# ProPrj_ftdi-jtag-xilinx_2025-03-12_v3.net
KiCad netlist of a schematic drawn in EasyEDA Pro
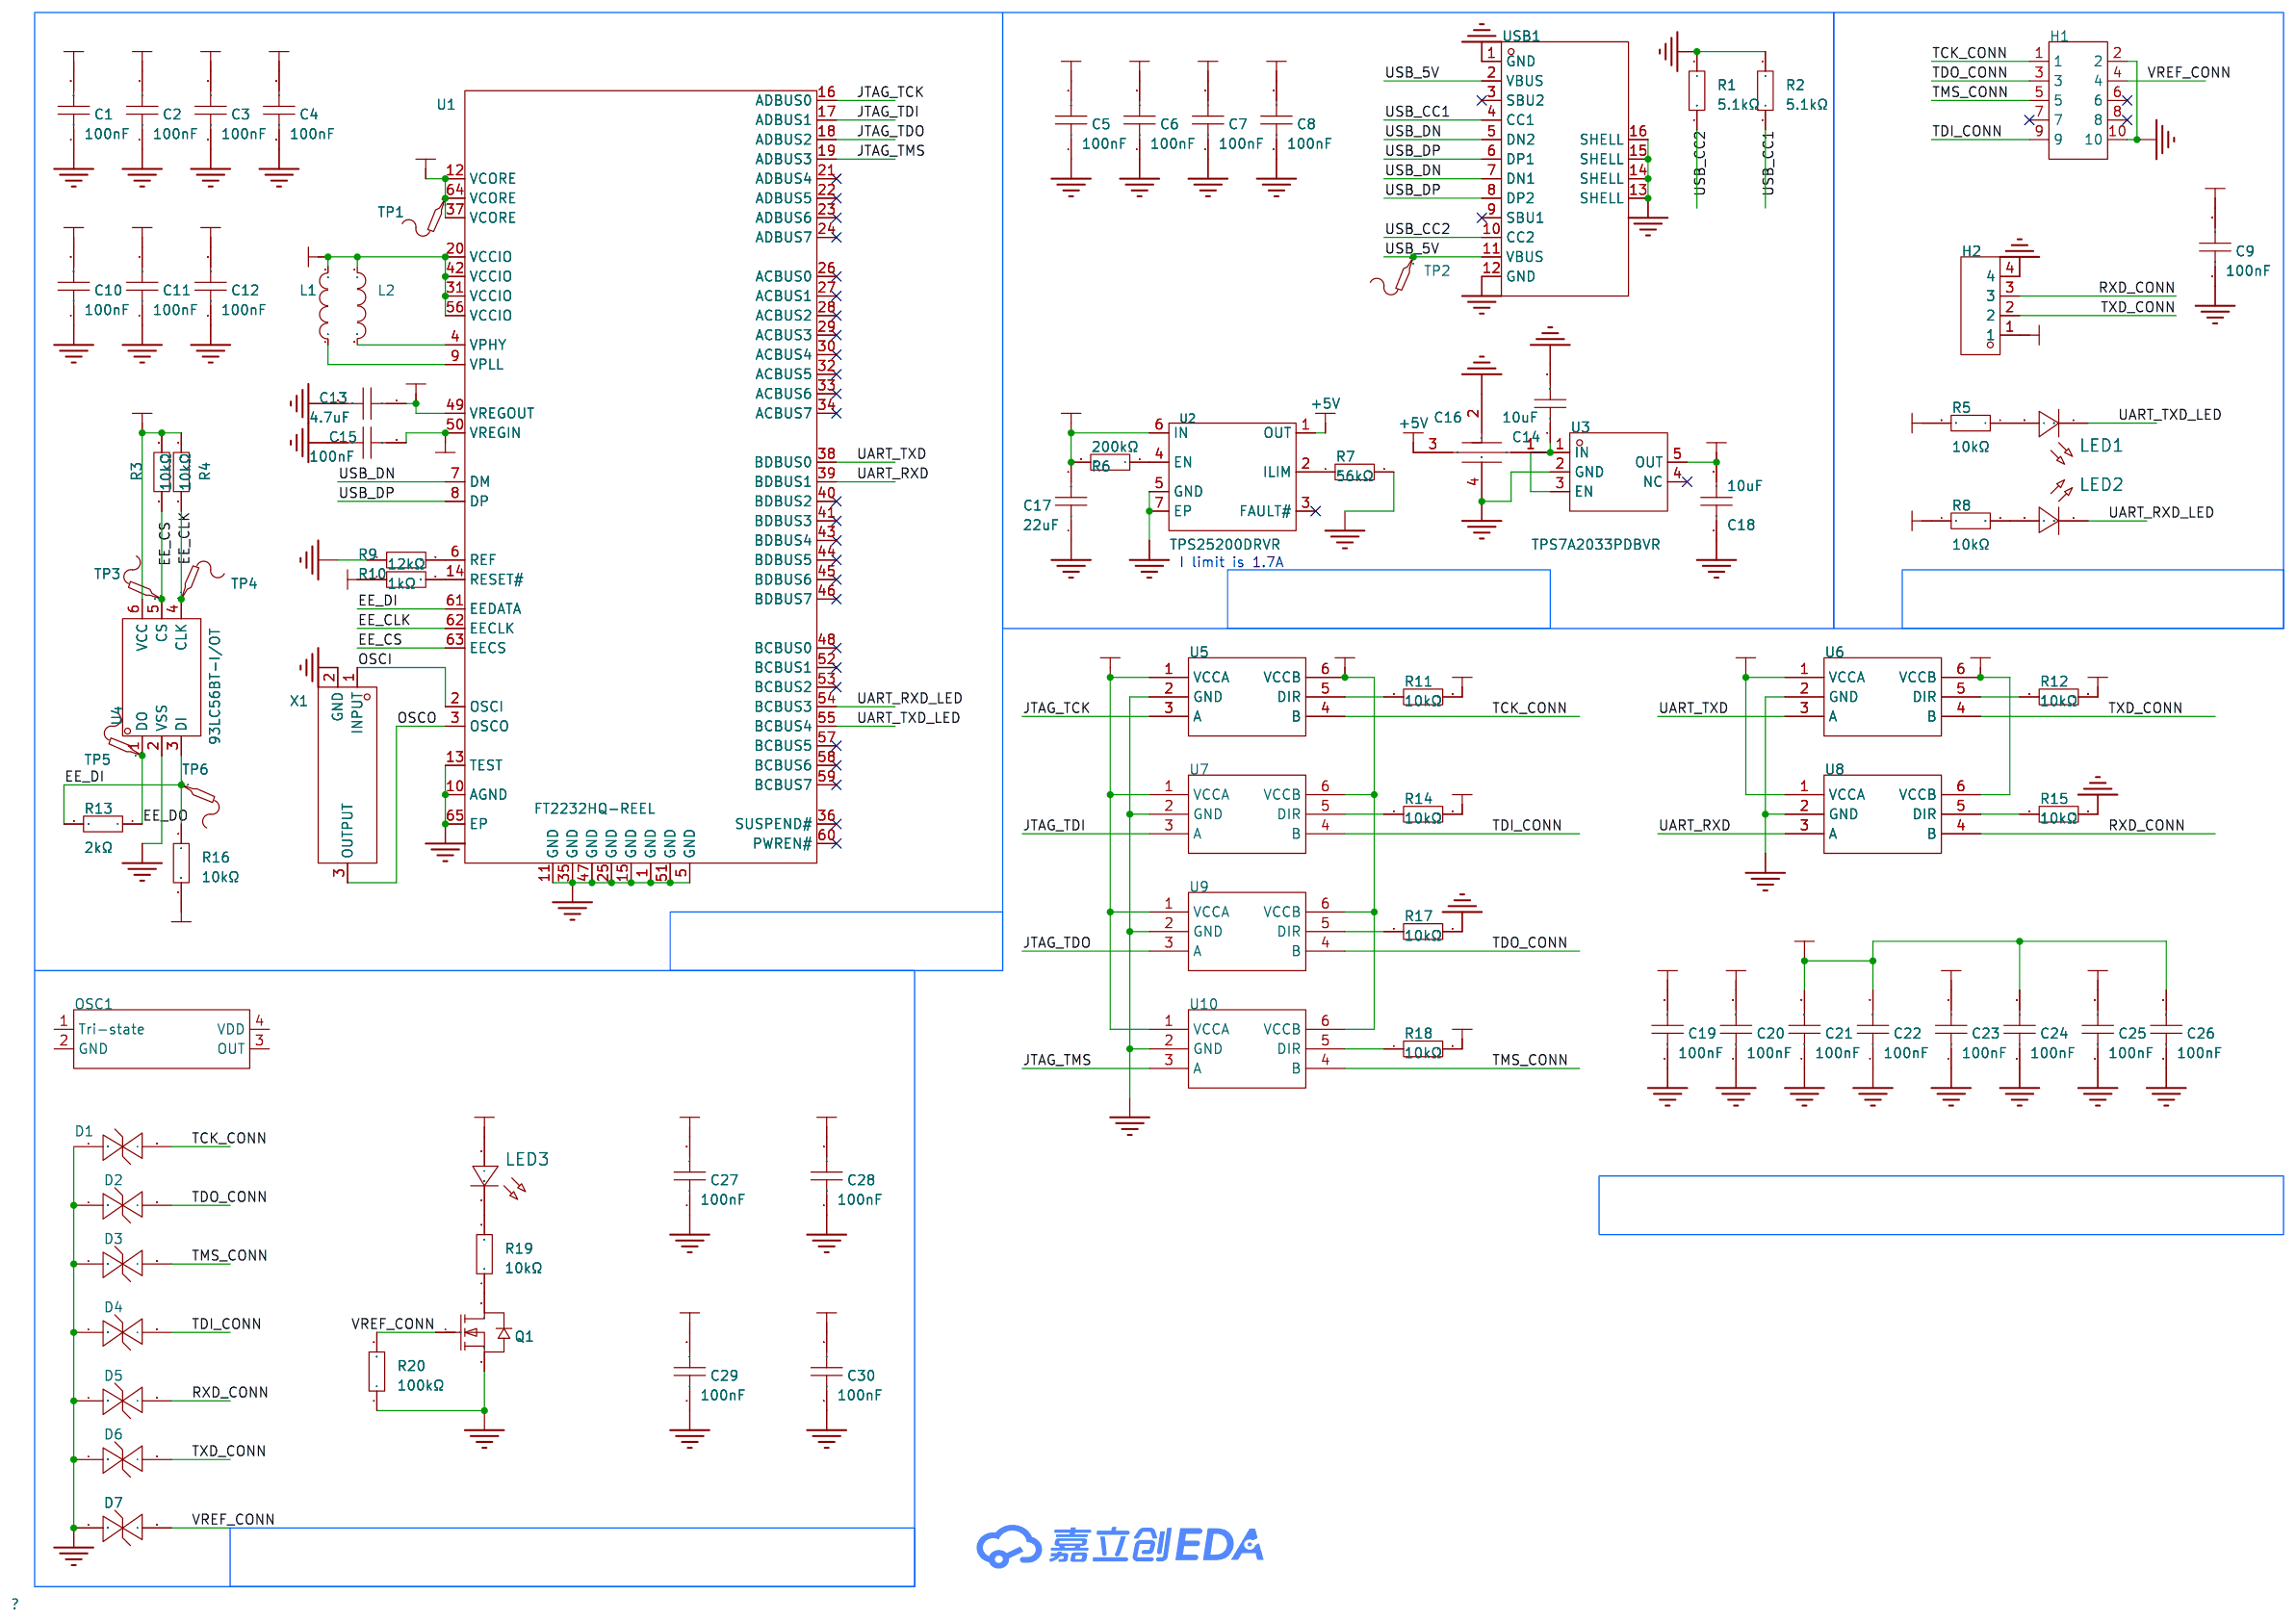
[diagram p0: schematic sheet]

(export (version "E")
  (design (tool "Eeschema 10.0.6"))
  (components
    (comp (ref "C1")
      (value "100nF")
      (footprint "easyedapro:C0603")
      (fields
        (field (name "Manufacturer Part") "CC0402KRX7R7BB104")
        (field (name "Manufacturer") "YAGEO(国巨)")
      )
      (libsource (lib "easyedapro") (part "CapAcitance"))
    )
    (comp (ref "C2")
      (value "100nF")
      (footprint "easyedapro:C0603")
      (fields
        (field (name "Manufacturer Part") "CC0402KRX7R7BB104")
        (field (name "Manufacturer") "YAGEO(国巨)")
      )
      (libsource (lib "easyedapro") (part "CapAcitance"))
    )
    (comp (ref "C3")
      (value "100nF")
      (footprint "easyedapro:C0603")
      (fields
        (field (name "Manufacturer Part") "CC0402KRX7R7BB104")
        (field (name "Manufacturer") "YAGEO(国巨)")
      )
      (libsource (lib "easyedapro") (part "CapAcitance"))
    )
    (comp (ref "C4")
      (value "100nF")
      (footprint "easyedapro:C0603")
      (fields
        (field (name "Manufacturer Part") "CC0402KRX7R7BB104")
        (field (name "Manufacturer") "YAGEO(国巨)")
      )
      (libsource (lib "easyedapro") (part "CapAcitance"))
    )
    (comp (ref "C5")
      (value "100nF")
      (footprint "easyedapro:C0603")
      (fields
        (field (name "Manufacturer Part") "CC0402KRX7R7BB104")
        (field (name "Manufacturer") "YAGEO(国巨)")
      )
      (libsource (lib "easyedapro") (part "CapAcitance"))
    )
    (comp (ref "C6")
      (value "100nF")
      (footprint "easyedapro:C0603")
      (fields
        (field (name "Manufacturer Part") "CC0402KRX7R7BB104")
        (field (name "Manufacturer") "YAGEO(国巨)")
      )
      (libsource (lib "easyedapro") (part "CapAcitance"))
    )
    (comp (ref "C7")
      (value "100nF")
      (footprint "easyedapro:C0603")
      (fields
        (field (name "Manufacturer Part") "CC0402KRX7R7BB104")
        (field (name "Manufacturer") "YAGEO(国巨)")
      )
      (libsource (lib "easyedapro") (part "CapAcitance"))
    )
    (comp (ref "C8")
      (value "100nF")
      (footprint "easyedapro:C0603")
      (fields
        (field (name "Manufacturer Part") "CC0402KRX7R7BB104")
        (field (name "Manufacturer") "YAGEO(国巨)")
      )
      (libsource (lib "easyedapro") (part "CapAcitance"))
    )
    (comp (ref "C9")
      (value "100nF")
      (footprint "easyedapro:C0603")
      (fields
        (field (name "Manufacturer Part") "CC0402KRX7R7BB104")
        (field (name "Manufacturer") "YAGEO(国巨)")
      )
      (libsource (lib "easyedapro") (part "CapAcitance"))
    )
    (comp (ref "C10")
      (value "100nF")
      (footprint "easyedapro:C0603")
      (fields
        (field (name "Manufacturer Part") "CC0402KRX7R7BB104")
        (field (name "Manufacturer") "YAGEO(国巨)")
      )
      (libsource (lib "easyedapro") (part "CapAcitance"))
    )
    (comp (ref "C11")
      (value "100nF")
      (footprint "easyedapro:C0603")
      (fields
        (field (name "Manufacturer Part") "CC0402KRX7R7BB104")
        (field (name "Manufacturer") "YAGEO(国巨)")
      )
      (libsource (lib "easyedapro") (part "CapAcitance"))
    )
    (comp (ref "C12")
      (value "100nF")
      (footprint "easyedapro:C0603")
      (fields
        (field (name "Manufacturer Part") "CC0402KRX7R7BB104")
        (field (name "Manufacturer") "YAGEO(国巨)")
      )
      (libsource (lib "easyedapro") (part "CapAcitance"))
    )
    (comp (ref "C13")
      (value "4.7uF")
      (footprint "easyedapro:C0603")
      (fields
        (field (name "Manufacturer Part") "CL05A475KP5NRNC")
        (field (name "Manufacturer") "SAMSUNG(三星)")
      )
      (libsource (lib "easyedapro") (part "CapAcitance"))
    )
    (comp (ref "C14")
      (value "10uF")
      (footprint "easyedapro:C0603")
      (fields
        (field (name "Manufacturer Part") "CL10A106MA8NRNC")
        (field (name "Manufacturer") "SAMSUNG(三星)")
      )
      (libsource (lib "easyedapro") (part "CapAcitance"))
    )
    (comp (ref "C15")
      (value "100nF")
      (footprint "easyedapro:C0603")
      (fields
        (field (name "Manufacturer Part") "CC0402KRX7R7BB104")
        (field (name "Manufacturer") "YAGEO(国巨)")
      )
      (libsource (lib "easyedapro") (part "CapAcitance"))
    )
    (comp (ref "C16")
      (value "NFM21PC104R1E3D")
      (footprint "easyedapro:CAP-SMD_4P-L2.0-W1.25")
      (description "电容量:100nF;精度:±20%;直流电阻:30mΩ;")
      (fields (field (name "Manufacturer") "muRata(村田)"))
      (libsource (lib "easyedapro") (part "NFM21PC104R1E3D"))
    )
    (comp (ref "C17")
      (value "22uF")
      (footprint "easyedapro:C0603")
      (fields
        (field (name "Manufacturer Part") "CGA0805X5R226M350MT")
        (field (name "Manufacturer") "HRE(芯声)")
      )
      (libsource (lib "easyedapro") (part "CapAcitance"))
    )
    (comp (ref "C18")
      (value "10uF")
      (footprint "easyedapro:C0603")
      (fields
        (field (name "Manufacturer Part") "CL10A106MA8NRNC")
        (field (name "Manufacturer") "SAMSUNG(三星)")
      )
      (libsource (lib "easyedapro") (part "CapAcitance"))
    )
    (comp (ref "C19")
      (value "100nF")
      (footprint "easyedapro:C0603")
      (fields
        (field (name "Manufacturer Part") "CC0402KRX7R7BB104")
        (field (name "Manufacturer") "YAGEO(国巨)")
      )
      (libsource (lib "easyedapro") (part "CapAcitance"))
    )
    (comp (ref "C20")
      (value "100nF")
      (footprint "easyedapro:C0603")
      (fields
        (field (name "Manufacturer Part") "CC0402KRX7R7BB104")
        (field (name "Manufacturer") "YAGEO(国巨)")
      )
      (libsource (lib "easyedapro") (part "CapAcitance"))
    )
    (comp (ref "C21")
      (value "100nF")
      (footprint "easyedapro:C0603")
      (fields
        (field (name "Manufacturer Part") "CC0402KRX7R7BB104")
        (field (name "Manufacturer") "YAGEO(国巨)")
      )
      (libsource (lib "easyedapro") (part "CapAcitance"))
    )
    (comp (ref "C22")
      (value "100nF")
      (footprint "easyedapro:C0603")
      (fields
        (field (name "Manufacturer Part") "CC0402KRX7R7BB104")
        (field (name "Manufacturer") "YAGEO(国巨)")
      )
      (libsource (lib "easyedapro") (part "CapAcitance"))
    )
    (comp (ref "C23")
      (value "100nF")
      (footprint "easyedapro:C0603")
      (fields
        (field (name "Manufacturer Part") "CC0402KRX7R7BB104")
        (field (name "Manufacturer") "YAGEO(国巨)")
      )
      (libsource (lib "easyedapro") (part "CapAcitance"))
    )
    (comp (ref "C24")
      (value "100nF")
      (footprint "easyedapro:C0603")
      (fields
        (field (name "Manufacturer Part") "CC0402KRX7R7BB104")
        (field (name "Manufacturer") "YAGEO(国巨)")
      )
      (libsource (lib "easyedapro") (part "CapAcitance"))
    )
    (comp (ref "C25")
      (value "100nF")
      (footprint "easyedapro:C0603")
      (fields
        (field (name "Manufacturer Part") "CC0402KRX7R7BB104")
        (field (name "Manufacturer") "YAGEO(国巨)")
      )
      (libsource (lib "easyedapro") (part "CapAcitance"))
    )
    (comp (ref "C26")
      (value "100nF")
      (footprint "easyedapro:C0603")
      (fields
        (field (name "Manufacturer Part") "CC0402KRX7R7BB104")
        (field (name "Manufacturer") "YAGEO(国巨)")
      )
      (libsource (lib "easyedapro") (part "CapAcitance"))
    )
    (comp (ref "C27")
      (value "100nF")
      (footprint "easyedapro:C0603")
      (fields
        (field (name "Manufacturer Part") "CC0402KRX7R7BB104")
        (field (name "Manufacturer") "YAGEO(国巨)")
      )
      (libsource (lib "easyedapro") (part "CapAcitance"))
    )
    (comp (ref "C28")
      (value "100nF")
      (footprint "easyedapro:C0603")
      (fields
        (field (name "Manufacturer Part") "CC0402KRX7R7BB104")
        (field (name "Manufacturer") "YAGEO(国巨)")
      )
      (libsource (lib "easyedapro") (part "CapAcitance"))
    )
    (comp (ref "C29")
      (value "100nF")
      (footprint "easyedapro:C0603")
      (fields
        (field (name "Manufacturer Part") "CC0402KRX7R7BB104")
        (field (name "Manufacturer") "YAGEO(国巨)")
      )
      (libsource (lib "easyedapro") (part "CapAcitance"))
    )
    (comp (ref "C30")
      (value "100nF")
      (footprint "easyedapro:C0603")
      (fields
        (field (name "Manufacturer Part") "CC0402KRX7R7BB104")
        (field (name "Manufacturer") "YAGEO(国巨)")
      )
      (libsource (lib "easyedapro") (part "CapAcitance"))
    )
    (comp (ref "D1")
      (value "H5VL10B")
      (footprint "easyedapro:SOD-882_L1.0-W0.6-BI")
      (description "极性:双向;反向截止电压(Vrwm):5V;最大钳位电压:10V;峰值脉冲电流(Ipp):5A;峰值脉冲功率(Ppp):50W;击穿电压:5.6V;")
      (fields (field (name "Manufacturer") "宏迦橙"))
      (libsource (lib "easyedapro") (part "H5VL10B"))
    )
    (comp (ref "D2")
      (value "H5VL10B")
      (footprint "easyedapro:SOD-882_L1.0-W0.6-BI")
      (description "极性:双向;反向截止电压(Vrwm):5V;最大钳位电压:10V;峰值脉冲电流(Ipp):5A;峰值脉冲功率(Ppp):50W;击穿电压:5.6V;")
      (fields (field (name "Manufacturer") "宏迦橙"))
      (libsource (lib "easyedapro") (part "H5VL10B"))
    )
    (comp (ref "D3")
      (value "H5VL10B")
      (footprint "easyedapro:SOD-882_L1.0-W0.6-BI")
      (description "极性:双向;反向截止电压(Vrwm):5V;最大钳位电压:10V;峰值脉冲电流(Ipp):5A;峰值脉冲功率(Ppp):50W;击穿电压:5.6V;")
      (fields (field (name "Manufacturer") "宏迦橙"))
      (libsource (lib "easyedapro") (part "H5VL10B"))
    )
    (comp (ref "D4")
      (value "H5VL10B")
      (footprint "easyedapro:SOD-882_L1.0-W0.6-BI")
      (description "极性:双向;反向截止电压(Vrwm):5V;最大钳位电压:10V;峰值脉冲电流(Ipp):5A;峰值脉冲功率(Ppp):50W;击穿电压:5.6V;")
      (fields (field (name "Manufacturer") "宏迦橙"))
      (libsource (lib "easyedapro") (part "H5VL10B"))
    )
    (comp (ref "D5")
      (value "H5VL10B")
      (footprint "easyedapro:SOD-882_L1.0-W0.6-BI")
      (description "极性:双向;反向截止电压(Vrwm):5V;最大钳位电压:10V;峰值脉冲电流(Ipp):5A;峰值脉冲功率(Ppp):50W;击穿电压:5.6V;")
      (fields (field (name "Manufacturer") "宏迦橙"))
      (libsource (lib "easyedapro") (part "H5VL10B"))
    )
    (comp (ref "D6")
      (value "H5VL10B")
      (footprint "easyedapro:SOD-882_L1.0-W0.6-BI")
      (description "极性:双向;反向截止电压(Vrwm):5V;最大钳位电压:10V;峰值脉冲电流(Ipp):5A;峰值脉冲功率(Ppp):50W;击穿电压:5.6V;")
      (fields (field (name "Manufacturer") "宏迦橙"))
      (libsource (lib "easyedapro") (part "H5VL10B"))
    )
    (comp (ref "D7")
      (value "H5VL10B")
      (footprint "easyedapro:SOD-882_L1.0-W0.6-BI")
      (description "极性:双向;反向截止电压(Vrwm):5V;最大钳位电压:10V;峰值脉冲电流(Ipp):5A;峰值脉冲功率(Ppp):50W;击穿电压:5.6V;")
      (fields (field (name "Manufacturer") "宏迦橙"))
      (libsource (lib "easyedapro") (part "H5VL10B"))
    )
    (comp (ref "H1")
      (value "PZ254-2-05-Z-8.5")
      (footprint "easyedapro:HDR-TH_10P-P2.54-V-M-R2-C5-S2.54")
      (fields (field (name "Manufacturer") "HCTL(华灿天禄)"))
      (libsource (lib "easyedapro") (part "PZ254-2-05-Z-8.5"))
    )
    (comp (ref "H2")
      (value "PZ254V-11-04P")
      (footprint "easyedapro:HDR-TH_4P-P2.54-V-M")
      (fields (field (name "Manufacturer") "XFCN(兴飞)"))
      (libsource (lib "easyedapro") (part "PZ254V-11-04P_C2691448"))
    )
    (comp (ref "L1")
      (value "BLM15PD121SN1D")
      (footprint "easyedapro:L0402")
      (description "标称阻抗@测试频率:120Ω@100MHz;误差:±25%;直流电阻(RDC):90mΩ;")
      (fields (field (name "Manufacturer") "muRata(村田)"))
      (libsource (lib "easyedapro") (part "BLM15PD121SN1D"))
    )
    (comp (ref "L2")
      (value "BLM15PD121SN1D")
      (footprint "easyedapro:L0402")
      (description "标称阻抗@测试频率:120Ω@100MHz;误差:±25%;直流电阻(RDC):90mΩ;")
      (fields (field (name "Manufacturer") "muRata(村田)"))
      (libsource (lib "easyedapro") (part "BLM15PD121SN1D"))
    )
    (comp (ref "LED1")
      (value "NCD0603Y1")
      (footprint "easyedapro:LED_0603")
      (fields (field (name "Manufacturer") "国星光电"))
      (libsource (lib "easyedapro") (part "LED_R"))
    )
    (comp (ref "LED2")
      (value "NCD0603Y1")
      (footprint "easyedapro:LED_0603")
      (fields (field (name "Manufacturer") "国星光电"))
      (libsource (lib "easyedapro") (part "LED_R"))
    )
    (comp (ref "LED3")
      (value "NCD0603Y1")
      (footprint "easyedapro:LED_0603")
      (fields (field (name "Manufacturer") "国星光电"))
      (libsource (lib "easyedapro") (part "LED_R"))
    )
    (comp (ref "OSC1")
      (value "12MHz")
      (footprint "easyedapro:OSC-SMD_4P-L2.0-W1.6-BL")
      (description "频率:12MHz;常温频差:±10ppm;输出模式:CMOS;工作电压:1.8V~3.3V;频率稳定度:±20ppm;")
      (fields
        (field (name "Manufacturer Part") "OT7EL89CJI-111YLC-12M")
        (field (name "Manufacturer") "YXC(扬兴晶振)")
      )
      (libsource (lib "easyedapro") (part "OT7EL89CJI-111YLC-12M"))
    )
    (comp (ref "Q1")
      (value "SI2302")
      (footprint "easyedapro:SOT-23-3_L2.9-W1.3-P1.90-LS2.4-BR")
      (description "类型:1个N沟道;漏源电压(Vdss):20V;连续漏极电流(Id):3A;导通电阻(RDS(on)):50mΩ@4.5V,3A;耗散功率(Pd):1W;阈值电压(Vgs(th)):1V;")
      (fields (field (name "Manufacturer") "YONGYUTAI(永裕泰)"))
      (libsource (lib "easyedapro") (part "SI2302_C2891732"))
    )
    (comp (ref "R1")
      (value "5.1kΩ")
      (footprint "easyedapro:R0603")
      (fields
        (field (name "Manufacturer Part") "0402WGF5101TCE")
        (field (name "Manufacturer") "UNI-ROYAL(厚声)")
      )
      (libsource (lib "easyedapro") (part "电阻"))
    )
    (comp (ref "R2")
      (value "5.1kΩ")
      (footprint "easyedapro:R0603")
      (fields
        (field (name "Manufacturer Part") "0402WGF5101TCE")
        (field (name "Manufacturer") "UNI-ROYAL(厚声)")
      )
      (libsource (lib "easyedapro") (part "电阻"))
    )
    (comp (ref "R3")
      (value "10kΩ")
      (footprint "easyedapro:R0603")
      (fields (field (name "Manufacturer Part") "RC0402FR-0710KL") (field (name "Manufacturer") "YAGEO(国巨)"))
      (libsource (lib "easyedapro") (part "电阻"))
    )
    (comp (ref "R4")
      (value "10kΩ")
      (footprint "easyedapro:R0603")
      (fields (field (name "Manufacturer Part") "RC0402FR-0710KL") (field (name "Manufacturer") "YAGEO(国巨)"))
      (libsource (lib "easyedapro") (part "电阻"))
    )
    (comp (ref "R5")
      (value "10kΩ")
      (footprint "easyedapro:R0603")
      (fields (field (name "Manufacturer Part") "RC0402FR-0710KL") (field (name "Manufacturer") "YAGEO(国巨)"))
      (libsource (lib "easyedapro") (part "电阻"))
    )
    (comp (ref "R6")
      (value "200kΩ")
      (footprint "easyedapro:R0603")
      (fields
        (field (name "Manufacturer Part") "0402WGF2003TCE")
        (field (name "Manufacturer") "UNI-ROYAL(厚声)")
      )
      (libsource (lib "easyedapro") (part "电阻"))
    )
    (comp (ref "R7")
      (value "56kΩ")
      (footprint "easyedapro:R0603")
      (fields
        (field (name "Manufacturer Part") "0402WGF5602TCE")
        (field (name "Manufacturer") "UNI-ROYAL(厚声)")
      )
      (libsource (lib "easyedapro") (part "电阻"))
    )
    (comp (ref "R8")
      (value "10kΩ")
      (footprint "easyedapro:R0603")
      (fields (field (name "Manufacturer Part") "RC0402FR-0710KL") (field (name "Manufacturer") "YAGEO(国巨)"))
      (libsource (lib "easyedapro") (part "电阻"))
    )
    (comp (ref "R9")
      (value "12kΩ")
      (footprint "easyedapro:R0603")
      (fields
        (field (name "Manufacturer Part") "0402WGF1202TCE")
        (field (name "Manufacturer") "UNI-ROYAL(厚声)")
      )
      (libsource (lib "easyedapro") (part "电阻"))
    )
    (comp (ref "R10")
      (value "1kΩ")
      (footprint "easyedapro:R0603")
      (fields
        (field (name "Manufacturer Part") "0402WGF1001TCE")
        (field (name "Manufacturer") "UNI-ROYAL(厚声)")
      )
      (libsource (lib "easyedapro") (part "电阻"))
    )
    (comp (ref "R11")
      (value "10kΩ")
      (footprint "easyedapro:R0603")
      (fields (field (name "Manufacturer Part") "RC0402FR-0710KL") (field (name "Manufacturer") "YAGEO(国巨)"))
      (libsource (lib "easyedapro") (part "电阻"))
    )
    (comp (ref "R12")
      (value "10kΩ")
      (footprint "easyedapro:R0603")
      (fields (field (name "Manufacturer Part") "RC0402FR-0710KL") (field (name "Manufacturer") "YAGEO(国巨)"))
      (libsource (lib "easyedapro") (part "电阻"))
    )
    (comp (ref "R13")
      (value "2kΩ")
      (footprint "easyedapro:R0603")
      (fields (field (name "Manufacturer Part") "FRC0402F2001TS") (field (name "Manufacturer") "FOJAN(富捷)"))
      (libsource (lib "easyedapro") (part "电阻"))
    )
    (comp (ref "R14")
      (value "10kΩ")
      (footprint "easyedapro:R0603")
      (fields (field (name "Manufacturer Part") "RC0402FR-0710KL") (field (name "Manufacturer") "YAGEO(国巨)"))
      (libsource (lib "easyedapro") (part "电阻"))
    )
    (comp (ref "R15")
      (value "10kΩ")
      (footprint "easyedapro:R0603")
      (fields (field (name "Manufacturer Part") "RC0402FR-0710KL") (field (name "Manufacturer") "YAGEO(国巨)"))
      (libsource (lib "easyedapro") (part "电阻"))
    )
    (comp (ref "R16")
      (value "10kΩ")
      (footprint "easyedapro:R0603")
      (fields (field (name "Manufacturer Part") "RC0402FR-0710KL") (field (name "Manufacturer") "YAGEO(国巨)"))
      (libsource (lib "easyedapro") (part "电阻"))
    )
    (comp (ref "R17")
      (value "10kΩ")
      (footprint "easyedapro:R0603")
      (fields (field (name "Manufacturer Part") "RC0402FR-0710KL") (field (name "Manufacturer") "YAGEO(国巨)"))
      (libsource (lib "easyedapro") (part "电阻"))
    )
    (comp (ref "R18")
      (value "10kΩ")
      (footprint "easyedapro:R0603")
      (fields (field (name "Manufacturer Part") "RC0402FR-0710KL") (field (name "Manufacturer") "YAGEO(国巨)"))
      (libsource (lib "easyedapro") (part "电阻"))
    )
    (comp (ref "R19")
      (value "10kΩ")
      (footprint "easyedapro:R0603")
      (fields (field (name "Manufacturer Part") "RC0402FR-0710KL") (field (name "Manufacturer") "YAGEO(国巨)"))
      (libsource (lib "easyedapro") (part "电阻"))
    )
    (comp (ref "R20")
      (value "100kΩ")
      (footprint "easyedapro:R0402")
      (description "电阻类型:厚膜电阻;阻值:100kΩ;精度:±1%;功率:62.5mW;最大工作电压:50V;温度系数:±100ppm/°C;")
      (fields
        (field (name "Manufacturer Part") "0402WGF1003TCE")
        (field (name "Manufacturer") "UNI-ROYAL(厚声)")
      )
      (libsource (lib "easyedapro") (part "0402WGF1003TCE"))
    )
    (comp (ref "TP1")
      (value "~")
      (footprint "easyedapro:Test-Point-0.5mm")
      (description "Test Point 测试点")
      (libsource (lib "easyedapro") (part "Test-Point"))
    )
    (comp (ref "TP2")
      (value "~")
      (footprint "easyedapro:Test-Point-0.5mm")
      (description "Test Point 测试点")
      (libsource (lib "easyedapro") (part "Test-Point"))
    )
    (comp (ref "TP3")
      (value "~")
      (footprint "easyedapro:Test-Point-0.5mm")
      (description "Test Point 测试点")
      (libsource (lib "easyedapro") (part "Test-Point"))
    )
    (comp (ref "TP4")
      (value "~")
      (footprint "easyedapro:Test-Point-0.5mm")
      (description "Test Point 测试点")
      (libsource (lib "easyedapro") (part "Test-Point"))
    )
    (comp (ref "TP5")
      (value "~")
      (footprint "easyedapro:Test-Point-0.5mm")
      (description "Test Point 测试点")
      (libsource (lib "easyedapro") (part "Test-Point"))
    )
    (comp (ref "TP6")
      (value "~")
      (footprint "easyedapro:Test-Point-0.5mm")
      (description "Test Point 测试点")
      (libsource (lib "easyedapro") (part "Test-Point"))
    )
    (comp (ref "U1")
      (value "FT2232HQ-REEL")
      (footprint "easyedapro:QFN-64_L9.0-W9.0-P0.50-TL-EP4.3")
      (description "应用功能:USB转UART；USB转FIFO;接口协议:UART;供电电压:3V~3.6V;")
      (fields (field (name "Manufacturer") "FTDI(飞特帝亚)"))
      (libsource (lib "easyedapro") (part "FT2232HQ-REEL"))
    )
    (comp (ref "U2")
      (value "TPS25200DRVR")
      (footprint "easyedapro:WSON-6_L2.0-W2.0-P0.65-TL-EP")
      (description "TPS25200 具有过压钳位的 6.5V/2.8A 电子保险丝")
      (fields (field (name "Manufacturer") "TI(德州仪器)"))
      (libsource (lib "easyedapro") (part "TPS25200DRVR"))
    )
    (comp (ref "U3")
      (value "TPS7A2033PDBVR")
      (footprint "easyedapro:SOT-23-5_L2.9-W1.6-P0.95-LS2.8-BR")
      (fields (field (name "Manufacturer") "TI(德州仪器)"))
      (libsource (lib "easyedapro") (part "TPS7A2033PDBVR"))
    )
    (comp (ref "U4")
      (value "93LC56BT-I/OT")
      (footprint "easyedapro:SOT-23-6_L2.9-W1.6-P0.95-LS2.8-BR")
      (fields (field (name "Manufacturer") "MICROCHIP(美国微芯)"))
      (libsource (lib "easyedapro") (part "93LC56BT-I/OT"))
    )
    (comp (ref "U5")
      (value "SN74LVC1T45DBVR")
      (footprint "easyedapro:SOT-23-6_L2.9-W1.6-P0.95-LS2.8-BR")
      (description "数据速率:420Mbps;电压(VCCA):1.65V~5.5V;电压(VCCB):1.65V~5.5V;电路数:1;每个电路通道数:1;")
      (fields (field (name "Manufacturer") "TI(德州仪器)"))
      (libsource (lib "easyedapro") (part "SN74LVC1T45DBVR"))
    )
    (comp (ref "U6")
      (value "SN74LVC1T45DBVR")
      (footprint "easyedapro:SOT-23-6_L2.9-W1.6-P0.95-LS2.8-BR")
      (description "数据速率:420Mbps;电压(VCCA):1.65V~5.5V;电压(VCCB):1.65V~5.5V;电路数:1;每个电路通道数:1;")
      (fields (field (name "Manufacturer") "TI(德州仪器)"))
      (libsource (lib "easyedapro") (part "SN74LVC1T45DBVR"))
    )
    (comp (ref "U7")
      (value "SN74LVC1T45DBVR")
      (footprint "easyedapro:SOT-23-6_L2.9-W1.6-P0.95-LS2.8-BR")
      (description "数据速率:420Mbps;电压(VCCA):1.65V~5.5V;电压(VCCB):1.65V~5.5V;电路数:1;每个电路通道数:1;")
      (fields (field (name "Manufacturer") "TI(德州仪器)"))
      (libsource (lib "easyedapro") (part "SN74LVC1T45DBVR"))
    )
    (comp (ref "U8")
      (value "SN74LVC1T45DBVR")
      (footprint "easyedapro:SOT-23-6_L2.9-W1.6-P0.95-LS2.8-BR")
      (description "数据速率:420Mbps;电压(VCCA):1.65V~5.5V;电压(VCCB):1.65V~5.5V;电路数:1;每个电路通道数:1;")
      (fields (field (name "Manufacturer") "TI(德州仪器)"))
      (libsource (lib "easyedapro") (part "SN74LVC1T45DBVR"))
    )
    (comp (ref "U9")
      (value "SN74LVC1T45DBVR")
      (footprint "easyedapro:SOT-23-6_L2.9-W1.6-P0.95-LS2.8-BR")
      (description "数据速率:420Mbps;电压(VCCA):1.65V~5.5V;电压(VCCB):1.65V~5.5V;电路数:1;每个电路通道数:1;")
      (fields (field (name "Manufacturer") "TI(德州仪器)"))
      (libsource (lib "easyedapro") (part "SN74LVC1T45DBVR"))
    )
    (comp (ref "U10")
      (value "SN74LVC1T45DBVR")
      (footprint "easyedapro:SOT-23-6_L2.9-W1.6-P0.95-LS2.8-BR")
      (description "数据速率:420Mbps;电压(VCCA):1.65V~5.5V;电压(VCCB):1.65V~5.5V;电路数:1;每个电路通道数:1;")
      (fields (field (name "Manufacturer") "TI(德州仪器)"))
      (libsource (lib "easyedapro") (part "SN74LVC1T45DBVR"))
    )
    (comp (ref "USB1")
      (value "TYPEC-302-BRP16SC16")
      (footprint "easyedapro:USB-C-SMD_TYPEC-302-BRP16SC16")
      (fields (field (name "Manufacturer") "XUNPU(讯普)"))
      (libsource (lib "easyedapro") (part "TYPEC-302-BRP16SC16"))
    )
    (comp (ref "X1")
      (value "12MHz")
      (footprint "easyedapro:CRYSTAL-SMD_3P-L3.2-W1.3-P1.2-BL")
      (description "频率:12MHz;内置负载电容:10pF;谐振阻抗:30Ω;")
      (fields
        (field (name "Manufacturer Part") "CSTNE12M0G52A000R0")
        (field (name "Manufacturer") "muRata(村田)")
      )
      (libsource (lib "easyedapro") (part "CSTNE12M0G52A000R0"))
    )
  )
  (nets
    (net (code "1") (name "+5V") (class "Default")
      (node (ref "C16") (pin "3") (pinfunction "OUT_3") (pintype "input"))
      (node (ref "U2") (pin "1") (pinfunction "OUT_1") (pintype "input"))
    )
    (net (code "2") (name "/EE_CLK") (class "Default")
      (node (ref "R4") (pin "2") (pinfunction "2_2") (pintype "input"))
      (node (ref "TP4") (pin "1") (pinfunction "1_1") (pintype "input"))
      (node (ref "U1") (pin "62") (pinfunction "EECLK_62") (pintype "input"))
      (node (ref "U4") (pin "4") (pinfunction "CLK_4") (pintype "input"))
    )
    (net (code "3") (name "/EE_CS") (class "Default")
      (node (ref "R3") (pin "2") (pinfunction "2_2") (pintype "input"))
      (node (ref "TP3") (pin "1") (pinfunction "1_1") (pintype "input"))
      (node (ref "U1") (pin "63") (pinfunction "EECS_63") (pintype "input"))
      (node (ref "U4") (pin "5") (pinfunction "CS_5") (pintype "input"))
    )
    (net (code "4") (name "/EE_DI") (class "Default")
      (node (ref "R13") (pin "2") (pinfunction "2_2") (pintype "input"))
      (node (ref "R16") (pin "1") (pinfunction "1_1") (pintype "input"))
      (node (ref "TP6") (pin "1") (pinfunction "1_1") (pintype "input"))
      (node (ref "U1") (pin "61") (pinfunction "EEDATA_61") (pintype "input"))
      (node (ref "U4") (pin "3") (pinfunction "DI_3") (pintype "input"))
    )
    (net (code "5") (name "/EE_DO") (class "Default")
      (node (ref "R13") (pin "1") (pinfunction "1_1") (pintype "input"))
      (node (ref "TP5") (pin "1") (pinfunction "1_1") (pintype "input"))
      (node (ref "U4") (pin "1") (pinfunction "DO_1") (pintype "input"))
    )
    (net (code "6") (name "/JTAG_TCK") (class "Default")
      (node (ref "U1") (pin "16") (pinfunction "ADBUS0_16") (pintype "input"))
      (node (ref "U5") (pin "3") (pinfunction "A_3") (pintype "unspecified"))
    )
    (net (code "7") (name "/JTAG_TDI") (class "Default")
      (node (ref "U1") (pin "17") (pinfunction "ADBUS1_17") (pintype "input"))
      (node (ref "U7") (pin "3") (pinfunction "A_3") (pintype "unspecified"))
    )
    (net (code "8") (name "/JTAG_TDO") (class "Default")
      (node (ref "U1") (pin "18") (pinfunction "ADBUS2_18") (pintype "input"))
      (node (ref "U9") (pin "3") (pinfunction "A_3") (pintype "unspecified"))
    )
    (net (code "9") (name "/JTAG_TMS") (class "Default")
      (node (ref "U1") (pin "19") (pinfunction "ADBUS3_19") (pintype "input"))
      (node (ref "U10") (pin "3") (pinfunction "A_3") (pintype "unspecified"))
    )
    (net (code "10") (name "/OSCI") (class "Default")
      (node (ref "U1") (pin "2") (pinfunction "OSCI_2") (pintype "input"))
      (node (ref "X1") (pin "1") (pinfunction "INPUT_1") (pintype "unspecified"))
    )
    (net (code "11") (name "/OSCO") (class "Default")
      (node (ref "U1") (pin "3") (pinfunction "OSCO_3") (pintype "input"))
      (node (ref "X1") (pin "3") (pinfunction "OUTPUT_3") (pintype "unspecified"))
    )
    (net (code "12") (name "/RXD_CONN") (class "Default")
      (node (ref "D5") (pin "2") (pinfunction "A_2") (pintype "unspecified"))
      (node (ref "H2") (pin "3") (pinfunction "3_3") (pintype "unspecified"))
      (node (ref "U8") (pin "4") (pinfunction "B_4") (pintype "unspecified"))
    )
    (net (code "13") (name "/TCK_CONN") (class "Default")
      (node (ref "D1") (pin "2") (pinfunction "A_2") (pintype "unspecified"))
      (node (ref "H1") (pin "1") (pinfunction "1_1") (pintype "unspecified"))
      (node (ref "U5") (pin "4") (pinfunction "B_4") (pintype "unspecified"))
    )
    (net (code "14") (name "/TDI_CONN") (class "Default")
      (node (ref "D4") (pin "2") (pinfunction "A_2") (pintype "unspecified"))
      (node (ref "H1") (pin "9") (pinfunction "9_9") (pintype "unspecified"))
      (node (ref "U7") (pin "4") (pinfunction "B_4") (pintype "unspecified"))
    )
    (net (code "15") (name "/TDO_CONN") (class "Default")
      (node (ref "D2") (pin "2") (pinfunction "A_2") (pintype "unspecified"))
      (node (ref "H1") (pin "3") (pinfunction "3_3") (pintype "unspecified"))
      (node (ref "U9") (pin "4") (pinfunction "B_4") (pintype "unspecified"))
    )
    (net (code "16") (name "/TMS_CONN") (class "Default")
      (node (ref "D3") (pin "2") (pinfunction "A_2") (pintype "unspecified"))
      (node (ref "H1") (pin "5") (pinfunction "5_5") (pintype "unspecified"))
      (node (ref "U10") (pin "4") (pinfunction "B_4") (pintype "unspecified"))
    )
    (net (code "17") (name "/TXD_CONN") (class "Default")
      (node (ref "D6") (pin "2") (pinfunction "A_2") (pintype "unspecified"))
      (node (ref "H2") (pin "2") (pinfunction "2_2") (pintype "unspecified"))
      (node (ref "U6") (pin "4") (pinfunction "B_4") (pintype "unspecified"))
    )
    (net (code "18") (name "/UART_RXD") (class "Default")
      (node (ref "U1") (pin "39") (pinfunction "BDBUS1_39") (pintype "input"))
      (node (ref "U8") (pin "3") (pinfunction "A_3") (pintype "unspecified"))
    )
    (net (code "19") (name "/UART_RXD_LED") (class "Default")
      (node (ref "LED2") (pin "1") (pinfunction "C_1") (pintype "input"))
      (node (ref "U1") (pin "54") (pinfunction "BCBUS3_54") (pintype "input"))
    )
    (net (code "20") (name "/UART_TXD") (class "Default")
      (node (ref "U1") (pin "38") (pinfunction "BDBUS0_38") (pintype "input"))
      (node (ref "U6") (pin "3") (pinfunction "A_3") (pintype "unspecified"))
    )
    (net (code "21") (name "/UART_TXD_LED") (class "Default")
      (node (ref "LED1") (pin "1") (pinfunction "C_1") (pintype "input"))
      (node (ref "U1") (pin "55") (pinfunction "BCBUS4_55") (pintype "input"))
    )
    (net (code "22") (name "/USB_CC1") (class "Default")
      (node (ref "R2") (pin "2") (pinfunction "2_2") (pintype "input"))
      (node (ref "USB1") (pin "4") (pinfunction "CC1_4") (pintype "unspecified"))
    )
    (net (code "23") (name "/USB_CC2") (class "Default")
      (node (ref "R1") (pin "2") (pinfunction "2_2") (pintype "input"))
      (node (ref "USB1") (pin "10") (pinfunction "CC2_10") (pintype "unspecified"))
    )
    (net (code "24") (name "/USB_DN") (class "Default")
      (node (ref "U1") (pin "7") (pinfunction "DM_7") (pintype "input"))
      (node (ref "USB1") (pin "5") (pinfunction "DN2_5") (pintype "unspecified"))
      (node (ref "USB1") (pin "7") (pinfunction "DN1_7") (pintype "unspecified"))
    )
    (net (code "25") (name "/USB_DP") (class "Default")
      (node (ref "U1") (pin "8") (pinfunction "DP_8") (pintype "input"))
      (node (ref "USB1") (pin "6") (pinfunction "DP1_6") (pintype "unspecified"))
      (node (ref "USB1") (pin "8") (pinfunction "DP2_8") (pintype "unspecified"))
    )
    (net (code "26") (name "3V3") (class "Default")
      (node (ref "C1") (pin "2") (pinfunction "2_2") (pintype "input"))
      (node (ref "C15") (pin "2") (pinfunction "2_2") (pintype "input"))
      (node (ref "C18") (pin "2") (pinfunction "2_2") (pintype "input"))
      (node (ref "C19") (pin "2") (pinfunction "2_2") (pintype "input"))
      (node (ref "C2") (pin "2") (pinfunction "2_2") (pintype "input"))
      (node (ref "C20") (pin "2") (pinfunction "2_2") (pintype "input"))
      (node (ref "C23") (pin "2") (pinfunction "2_2") (pintype "input"))
      (node (ref "C25") (pin "2") (pinfunction "2_2") (pintype "input"))
      (node (ref "C27") (pin "2") (pinfunction "2_2") (pintype "input"))
      (node (ref "C29") (pin "2") (pinfunction "2_2") (pintype "input"))
      (node (ref "C3") (pin "2") (pinfunction "2_2") (pintype "input"))
      (node (ref "C4") (pin "2") (pinfunction "2_2") (pintype "input"))
      (node (ref "C5") (pin "2") (pinfunction "2_2") (pintype "input"))
      (node (ref "C6") (pin "2") (pinfunction "2_2") (pintype "input"))
      (node (ref "C7") (pin "2") (pinfunction "2_2") (pintype "input"))
      (node (ref "C8") (pin "2") (pinfunction "2_2") (pintype "input"))
      (node (ref "H2") (pin "1") (pinfunction "1_1") (pintype "unspecified"))
      (node (ref "L1") (pin "2") (pinfunction "2_2") (pintype "input"))
      (node (ref "L2") (pin "1") (pinfunction "1_1") (pintype "input"))
      (node (ref "LED3") (pin "2") (pinfunction "A_2") (pintype "input"))
      (node (ref "R10") (pin "1") (pinfunction "1_1") (pintype "input"))
      (node (ref "R11") (pin "2") (pinfunction "2_2") (pintype "input"))
      (node (ref "R12") (pin "2") (pinfunction "2_2") (pintype "input"))
      (node (ref "R14") (pin "2") (pinfunction "2_2") (pintype "input"))
      (node (ref "R16") (pin "2") (pinfunction "2_2") (pintype "input"))
      (node (ref "R18") (pin "2") (pinfunction "2_2") (pintype "input"))
      (node (ref "R3") (pin "1") (pinfunction "1_1") (pintype "input"))
      (node (ref "R4") (pin "1") (pinfunction "1_1") (pintype "input"))
      (node (ref "R5") (pin "2") (pinfunction "2_2") (pintype "input"))
      (node (ref "R8") (pin "1") (pinfunction "1_1") (pintype "input"))
      (node (ref "U1") (pin "20") (pinfunction "VCCIO_20") (pintype "input"))
      (node (ref "U1") (pin "31") (pinfunction "VCCIO_31") (pintype "input"))
      (node (ref "U1") (pin "42") (pinfunction "VCCIO_42") (pintype "input"))
      (node (ref "U1") (pin "50") (pinfunction "VREGIN_50") (pintype "input"))
      (node (ref "U1") (pin "56") (pinfunction "VCCIO_56") (pintype "input"))
      (node (ref "U10") (pin "1") (pinfunction "VCCA_1") (pintype "unspecified"))
      (node (ref "U3") (pin "5") (pinfunction "OUT_5") (pintype "input"))
      (node (ref "U4") (pin "6") (pinfunction "VCC_6") (pintype "input"))
      (node (ref "U5") (pin "1") (pinfunction "VCCA_1") (pintype "unspecified"))
      (node (ref "U6") (pin "1") (pinfunction "VCCA_1") (pintype "unspecified"))
      (node (ref "U7") (pin "1") (pinfunction "VCCA_1") (pintype "unspecified"))
      (node (ref "U8") (pin "1") (pinfunction "VCCA_1") (pintype "unspecified"))
      (node (ref "U9") (pin "1") (pinfunction "VCCA_1") (pintype "unspecified"))
    )
    (net (code "27") (name "GND") (class "Default")
      (node (ref "C1") (pin "1") (pinfunction "1_1") (pintype "input"))
      (node (ref "C10") (pin "1") (pinfunction "1_1") (pintype "input"))
      (node (ref "C11") (pin "1") (pinfunction "1_1") (pintype "input"))
      (node (ref "C12") (pin "1") (pinfunction "1_1") (pintype "input"))
      (node (ref "C13") (pin "2") (pinfunction "2_2") (pintype "input"))
      (node (ref "C14") (pin "2") (pinfunction "2_2") (pintype "input"))
      (node (ref "C15") (pin "1") (pinfunction "1_1") (pintype "input"))
      (node (ref "C16") (pin "2") (pinfunction "GND_2") (pintype "input"))
      (node (ref "C16") (pin "4") (pinfunction "GND_4") (pintype "input"))
      (node (ref "C17") (pin "1") (pinfunction "1_1") (pintype "input"))
      (node (ref "C18") (pin "1") (pinfunction "1_1") (pintype "input"))
      (node (ref "C19") (pin "1") (pinfunction "1_1") (pintype "input"))
      (node (ref "C2") (pin "1") (pinfunction "1_1") (pintype "input"))
      (node (ref "C20") (pin "1") (pinfunction "1_1") (pintype "input"))
      (node (ref "C21") (pin "1") (pinfunction "1_1") (pintype "input"))
      (node (ref "C22") (pin "1") (pinfunction "1_1") (pintype "input"))
      (node (ref "C23") (pin "1") (pinfunction "1_1") (pintype "input"))
      (node (ref "C24") (pin "1") (pinfunction "1_1") (pintype "input"))
      (node (ref "C25") (pin "1") (pinfunction "1_1") (pintype "input"))
      (node (ref "C26") (pin "1") (pinfunction "1_1") (pintype "input"))
      (node (ref "C27") (pin "1") (pinfunction "1_1") (pintype "input"))
      (node (ref "C28") (pin "1") (pinfunction "1_1") (pintype "input"))
      (node (ref "C29") (pin "1") (pinfunction "1_1") (pintype "input"))
      (node (ref "C3") (pin "1") (pinfunction "1_1") (pintype "input"))
      (node (ref "C30") (pin "1") (pinfunction "1_1") (pintype "input"))
      (node (ref "C4") (pin "1") (pinfunction "1_1") (pintype "input"))
      (node (ref "C5") (pin "1") (pinfunction "1_1") (pintype "input"))
      (node (ref "C6") (pin "1") (pinfunction "1_1") (pintype "input"))
      (node (ref "C7") (pin "1") (pinfunction "1_1") (pintype "input"))
      (node (ref "C8") (pin "1") (pinfunction "1_1") (pintype "input"))
      (node (ref "C9") (pin "1") (pinfunction "1_1") (pintype "input"))
      (node (ref "D1") (pin "1") (pinfunction "C_1") (pintype "unspecified"))
      (node (ref "D2") (pin "1") (pinfunction "C_1") (pintype "unspecified"))
      (node (ref "D3") (pin "1") (pinfunction "C_1") (pintype "unspecified"))
      (node (ref "D4") (pin "1") (pinfunction "C_1") (pintype "unspecified"))
      (node (ref "D5") (pin "1") (pinfunction "C_1") (pintype "unspecified"))
      (node (ref "D6") (pin "1") (pinfunction "C_1") (pintype "unspecified"))
      (node (ref "D7") (pin "1") (pinfunction "C_1") (pintype "unspecified"))
      (node (ref "H1") (pin "10") (pinfunction "10_10") (pintype "unspecified"))
      (node (ref "H1") (pin "2") (pinfunction "2_2") (pintype "unspecified"))
      (node (ref "H2") (pin "4") (pinfunction "4_4") (pintype "unspecified"))
      (node (ref "Q1") (pin "2") (pinfunction "S_2") (pintype "unspecified"))
      (node (ref "R1") (pin "1") (pinfunction "1_1") (pintype "input"))
      (node (ref "R15") (pin "2") (pinfunction "2_2") (pintype "input"))
      (node (ref "R17") (pin "2") (pinfunction "2_2") (pintype "input"))
      (node (ref "R2") (pin "1") (pinfunction "1_1") (pintype "input"))
      (node (ref "R20") (pin "1") (pinfunction "1_1") (pintype "input"))
      (node (ref "R7") (pin "2") (pinfunction "2_2") (pintype "input"))
      (node (ref "R9") (pin "1") (pinfunction "1_1") (pintype "input"))
      (node (ref "U1") (pin "1") (pinfunction "GND_1") (pintype "input"))
      (node (ref "U1") (pin "10") (pinfunction "AGND_10") (pintype "input"))
      (node (ref "U1") (pin "11") (pinfunction "GND_11") (pintype "input"))
      (node (ref "U1") (pin "13") (pinfunction "TEST_13") (pintype "input"))
      (node (ref "U1") (pin "15") (pinfunction "GND_15") (pintype "input"))
      (node (ref "U1") (pin "25") (pinfunction "GND_25") (pintype "input"))
      (node (ref "U1") (pin "35") (pinfunction "GND_35") (pintype "input"))
      (node (ref "U1") (pin "47") (pinfunction "GND_47") (pintype "input"))
      (node (ref "U1") (pin "5") (pinfunction "GND_5") (pintype "input"))
      (node (ref "U1") (pin "51") (pinfunction "GND_51") (pintype "input"))
      (node (ref "U1") (pin "65") (pinfunction "EP_65") (pintype "input"))
      (node (ref "U10") (pin "2") (pinfunction "GND_2") (pintype "unspecified"))
      (node (ref "U2") (pin "5") (pinfunction "GND_5") (pintype "input"))
      (node (ref "U2") (pin "7") (pinfunction "EP_7") (pintype "input"))
      (node (ref "U3") (pin "2") (pinfunction "GND_2") (pintype "input"))
      (node (ref "U4") (pin "2") (pinfunction "VSS_2") (pintype "input"))
      (node (ref "U5") (pin "2") (pinfunction "GND_2") (pintype "unspecified"))
      (node (ref "U6") (pin "2") (pinfunction "GND_2") (pintype "unspecified"))
      (node (ref "U7") (pin "2") (pinfunction "GND_2") (pintype "unspecified"))
      (node (ref "U8") (pin "2") (pinfunction "GND_2") (pintype "unspecified"))
      (node (ref "U9") (pin "2") (pinfunction "GND_2") (pintype "unspecified"))
      (node (ref "USB1") (pin "1") (pinfunction "GND_1") (pintype "unspecified"))
      (node (ref "USB1") (pin "12") (pinfunction "GND_12") (pintype "unspecified"))
      (node (ref "USB1") (pin "13") (pinfunction "SHELL_13") (pintype "unspecified"))
      (node (ref "USB1") (pin "14") (pinfunction "SHELL_14") (pintype "unspecified"))
      (node (ref "USB1") (pin "15") (pinfunction "SHELL_15") (pintype "unspecified"))
      (node (ref "USB1") (pin "16") (pinfunction "SHELL_16") (pintype "unspecified"))
      (node (ref "X1") (pin "2") (pinfunction "GND_2") (pintype "unspecified"))
    )
    (net (code "28") (name "Net-(C16-IN)") (class "Default")
      (node (ref "C14") (pin "1") (pinfunction "1_1") (pintype "input"))
      (node (ref "C16") (pin "1") (pinfunction "IN_1") (pintype "input"))
      (node (ref "U3") (pin "1") (pinfunction "IN_1") (pintype "input"))
      (node (ref "U3") (pin "3") (pinfunction "EN_3") (pintype "input"))
    )
    (net (code "29") (name "Net-(LED1-A)") (class "Default")
      (node (ref "LED1") (pin "2") (pinfunction "A_2") (pintype "input"))
      (node (ref "R5") (pin "1") (pinfunction "1_1") (pintype "input"))
    )
    (net (code "30") (name "Net-(LED2-A)") (class "Default")
      (node (ref "LED2") (pin "2") (pinfunction "A_2") (pintype "input"))
      (node (ref "R8") (pin "2") (pinfunction "2_2") (pintype "input"))
    )
    (net (code "31") (name "Net-(LED3-C)") (class "Default")
      (node (ref "LED3") (pin "1") (pinfunction "C_1") (pintype "input"))
      (node (ref "R19") (pin "2") (pinfunction "2_2") (pintype "input"))
    )
    (net (code "32") (name "Net-(Q1-D)") (class "Default")
      (node (ref "Q1") (pin "3") (pinfunction "D_3") (pintype "unspecified"))
      (node (ref "R19") (pin "1") (pinfunction "1_1") (pintype "input"))
    )
    (net (code "33") (name "Net-(U1-REF)") (class "Default")
      (node (ref "R9") (pin "2") (pinfunction "2_2") (pintype "input"))
      (node (ref "U1") (pin "6") (pinfunction "REF_6") (pintype "input"))
    )
    (net (code "34") (name "Net-(U1-RESET#)") (class "Default")
      (node (ref "R10") (pin "2") (pinfunction "2_2") (pintype "input"))
      (node (ref "U1") (pin "14") (pinfunction "RESET#_14") (pintype "input"))
    )
    (net (code "35") (name "Net-(U1-VPHY)") (class "Default")
      (node (ref "L2") (pin "2") (pinfunction "2_2") (pintype "input"))
      (node (ref "U1") (pin "4") (pinfunction "VPHY_4") (pintype "input"))
    )
    (net (code "36") (name "Net-(U1-VPLL)") (class "Default")
      (node (ref "L1") (pin "1") (pinfunction "1_1") (pintype "input"))
      (node (ref "U1") (pin "9") (pinfunction "VPLL_9") (pintype "input"))
    )
    (net (code "37") (name "Net-(U2-EN)") (class "Default")
      (node (ref "R6") (pin "1") (pinfunction "1_1") (pintype "input"))
      (node (ref "U2") (pin "4") (pinfunction "EN_4") (pintype "input"))
    )
    (net (code "38") (name "Net-(U2-ILIM)") (class "Default")
      (node (ref "R7") (pin "1") (pinfunction "1_1") (pintype "input"))
      (node (ref "U2") (pin "2") (pinfunction "ILIM_2") (pintype "input"))
    )
    (net (code "39") (name "Net-(U5-DIR)") (class "Default")
      (node (ref "R11") (pin "1") (pinfunction "1_1") (pintype "input"))
      (node (ref "U5") (pin "5") (pinfunction "DIR_5") (pintype "unspecified"))
    )
    (net (code "40") (name "Net-(U6-DIR)") (class "Default")
      (node (ref "R12") (pin "1") (pinfunction "1_1") (pintype "input"))
      (node (ref "U6") (pin "5") (pinfunction "DIR_5") (pintype "unspecified"))
    )
    (net (code "41") (name "Net-(U7-DIR)") (class "Default")
      (node (ref "R14") (pin "1") (pinfunction "1_1") (pintype "input"))
      (node (ref "U7") (pin "5") (pinfunction "DIR_5") (pintype "unspecified"))
    )
    (net (code "42") (name "Net-(U8-DIR)") (class "Default")
      (node (ref "R15") (pin "1") (pinfunction "1_1") (pintype "input"))
      (node (ref "U8") (pin "5") (pinfunction "DIR_5") (pintype "unspecified"))
    )
    (net (code "43") (name "Net-(U9-DIR)") (class "Default")
      (node (ref "R17") (pin "1") (pinfunction "1_1") (pintype "input"))
      (node (ref "U9") (pin "5") (pinfunction "DIR_5") (pintype "unspecified"))
    )
    (net (code "44") (name "Net-(U10-DIR)") (class "Default")
      (node (ref "R18") (pin "1") (pinfunction "1_1") (pintype "input"))
      (node (ref "U10") (pin "5") (pinfunction "DIR_5") (pintype "unspecified"))
    )
    (net (code "45") (name "USB_5V") (class "Default")
      (node (ref "C17") (pin "2") (pinfunction "2_2") (pintype "input"))
      (node (ref "R6") (pin "2") (pinfunction "2_2") (pintype "input"))
      (node (ref "TP2") (pin "1") (pinfunction "1_1") (pintype "input"))
      (node (ref "U2") (pin "6") (pinfunction "IN_6") (pintype "input"))
      (node (ref "USB1") (pin "11") (pinfunction "VBUS_11") (pintype "unspecified"))
      (node (ref "USB1") (pin "2") (pinfunction "VBUS_2") (pintype "unspecified"))
    )
    (net (code "46") (name "VCORE") (class "Default")
      (node (ref "C10") (pin "2") (pinfunction "2_2") (pintype "input"))
      (node (ref "C11") (pin "2") (pinfunction "2_2") (pintype "input"))
      (node (ref "C12") (pin "2") (pinfunction "2_2") (pintype "input"))
      (node (ref "C13") (pin "1") (pinfunction "1_1") (pintype "input"))
      (node (ref "TP1") (pin "1") (pinfunction "1_1") (pintype "input"))
      (node (ref "U1") (pin "12") (pinfunction "VCORE_12") (pintype "input"))
      (node (ref "U1") (pin "37") (pinfunction "VCORE_37") (pintype "input"))
      (node (ref "U1") (pin "49") (pinfunction "VREGOUT_49") (pintype "input"))
      (node (ref "U1") (pin "64") (pinfunction "VCORE_64") (pintype "input"))
    )
    (net (code "47") (name "VREF_CONN") (class "Default")
      (node (ref "C21") (pin "2") (pinfunction "2_2") (pintype "input"))
      (node (ref "C22") (pin "2") (pinfunction "2_2") (pintype "input"))
      (node (ref "C24") (pin "2") (pinfunction "2_2") (pintype "input"))
      (node (ref "C26") (pin "2") (pinfunction "2_2") (pintype "input"))
      (node (ref "C28") (pin "2") (pinfunction "2_2") (pintype "input"))
      (node (ref "C30") (pin "2") (pinfunction "2_2") (pintype "input"))
      (node (ref "C9") (pin "2") (pinfunction "2_2") (pintype "input"))
      (node (ref "D7") (pin "2") (pinfunction "A_2") (pintype "unspecified"))
      (node (ref "H1") (pin "4") (pinfunction "4_4") (pintype "unspecified"))
      (node (ref "Q1") (pin "1") (pinfunction "G_1") (pintype "unspecified"))
      (node (ref "R20") (pin "2") (pinfunction "2_2") (pintype "input"))
      (node (ref "U10") (pin "6") (pinfunction "VCCB_6") (pintype "unspecified"))
      (node (ref "U5") (pin "6") (pinfunction "VCCB_6") (pintype "unspecified"))
      (node (ref "U6") (pin "6") (pinfunction "VCCB_6") (pintype "unspecified"))
      (node (ref "U7") (pin "6") (pinfunction "VCCB_6") (pintype "unspecified"))
      (node (ref "U8") (pin "6") (pinfunction "VCCB_6") (pintype "unspecified"))
      (node (ref "U9") (pin "6") (pinfunction "VCCB_6") (pintype "unspecified"))
    )
    (net (code "48") (name "unconnected-(H1-Pad6)") (class "Default")
      (node (ref "H1") (pin "6") (pinfunction "6_6") (pintype "unspecified+no_connect"))
    )
    (net (code "49") (name "unconnected-(H1-Pad7)") (class "Default")
      (node (ref "H1") (pin "7") (pinfunction "7_7") (pintype "unspecified+no_connect"))
    )
    (net (code "50") (name "unconnected-(H1-Pad8)") (class "Default")
      (node (ref "H1") (pin "8") (pinfunction "8_8") (pintype "unspecified+no_connect"))
    )
    (net (code "51") (name "unconnected-(OSC1-GND-Pad2)") (class "Default")
      (node (ref "OSC1") (pin "2") (pinfunction "GND_2") (pintype "unspecified"))
    )
    (net (code "52") (name "unconnected-(OSC1-OUT-Pad3)") (class "Default")
      (node (ref "OSC1") (pin "3") (pinfunction "OUT_3") (pintype "unspecified"))
    )
    (net (code "53") (name "unconnected-(OSC1-Tri-state-Pad1)") (class "Default")
      (node (ref "OSC1") (pin "1") (pinfunction "Tri-state_1") (pintype "unspecified"))
    )
    (net (code "54") (name "unconnected-(OSC1-VDD-Pad4)") (class "Default")
      (node (ref "OSC1") (pin "4") (pinfunction "VDD_4") (pintype "unspecified"))
    )
    (net (code "55") (name "unconnected-(U1-ACBUS0-Pad26)") (class "Default")
      (node (ref "U1") (pin "26") (pinfunction "ACBUS0_26") (pintype "input+no_connect"))
    )
    (net (code "56") (name "unconnected-(U1-ACBUS1-Pad27)") (class "Default")
      (node (ref "U1") (pin "27") (pinfunction "ACBUS1_27") (pintype "input+no_connect"))
    )
    (net (code "57") (name "unconnected-(U1-ACBUS2-Pad28)") (class "Default")
      (node (ref "U1") (pin "28") (pinfunction "ACBUS2_28") (pintype "input+no_connect"))
    )
    (net (code "58") (name "unconnected-(U1-ACBUS3-Pad29)") (class "Default")
      (node (ref "U1") (pin "29") (pinfunction "ACBUS3_29") (pintype "input+no_connect"))
    )
    (net (code "59") (name "unconnected-(U1-ACBUS4-Pad30)") (class "Default")
      (node (ref "U1") (pin "30") (pinfunction "ACBUS4_30") (pintype "input+no_connect"))
    )
    (net (code "60") (name "unconnected-(U1-ACBUS5-Pad32)") (class "Default")
      (node (ref "U1") (pin "32") (pinfunction "ACBUS5_32") (pintype "input+no_connect"))
    )
    (net (code "61") (name "unconnected-(U1-ACBUS6-Pad33)") (class "Default")
      (node (ref "U1") (pin "33") (pinfunction "ACBUS6_33") (pintype "input+no_connect"))
    )
    (net (code "62") (name "unconnected-(U1-ACBUS7-Pad34)") (class "Default")
      (node (ref "U1") (pin "34") (pinfunction "ACBUS7_34") (pintype "input+no_connect"))
    )
    (net (code "63") (name "unconnected-(U1-ADBUS4-Pad21)") (class "Default")
      (node (ref "U1") (pin "21") (pinfunction "ADBUS4_21") (pintype "input+no_connect"))
    )
    (net (code "64") (name "unconnected-(U1-ADBUS5-Pad22)") (class "Default")
      (node (ref "U1") (pin "22") (pinfunction "ADBUS5_22") (pintype "input+no_connect"))
    )
    (net (code "65") (name "unconnected-(U1-ADBUS6-Pad23)") (class "Default")
      (node (ref "U1") (pin "23") (pinfunction "ADBUS6_23") (pintype "input+no_connect"))
    )
    (net (code "66") (name "unconnected-(U1-ADBUS7-Pad24)") (class "Default")
      (node (ref "U1") (pin "24") (pinfunction "ADBUS7_24") (pintype "input+no_connect"))
    )
    (net (code "67") (name "unconnected-(U1-BCBUS0-Pad48)") (class "Default")
      (node (ref "U1") (pin "48") (pinfunction "BCBUS0_48") (pintype "input+no_connect"))
    )
    (net (code "68") (name "unconnected-(U1-BCBUS1-Pad52)") (class "Default")
      (node (ref "U1") (pin "52") (pinfunction "BCBUS1_52") (pintype "input+no_connect"))
    )
    (net (code "69") (name "unconnected-(U1-BCBUS2-Pad53)") (class "Default")
      (node (ref "U1") (pin "53") (pinfunction "BCBUS2_53") (pintype "input+no_connect"))
    )
    (net (code "70") (name "unconnected-(U1-BCBUS5-Pad57)") (class "Default")
      (node (ref "U1") (pin "57") (pinfunction "BCBUS5_57") (pintype "input+no_connect"))
    )
    (net (code "71") (name "unconnected-(U1-BCBUS6-Pad58)") (class "Default")
      (node (ref "U1") (pin "58") (pinfunction "BCBUS6_58") (pintype "input+no_connect"))
    )
    (net (code "72") (name "unconnected-(U1-BCBUS7-Pad59)") (class "Default")
      (node (ref "U1") (pin "59") (pinfunction "BCBUS7_59") (pintype "input+no_connect"))
    )
    (net (code "73") (name "unconnected-(U1-BDBUS2-Pad40)") (class "Default")
      (node (ref "U1") (pin "40") (pinfunction "BDBUS2_40") (pintype "input+no_connect"))
    )
    (net (code "74") (name "unconnected-(U1-BDBUS3-Pad41)") (class "Default")
      (node (ref "U1") (pin "41") (pinfunction "BDBUS3_41") (pintype "input+no_connect"))
    )
    (net (code "75") (name "unconnected-(U1-BDBUS4-Pad43)") (class "Default")
      (node (ref "U1") (pin "43") (pinfunction "BDBUS4_43") (pintype "input+no_connect"))
    )
    (net (code "76") (name "unconnected-(U1-BDBUS5-Pad44)") (class "Default")
      (node (ref "U1") (pin "44") (pinfunction "BDBUS5_44") (pintype "input+no_connect"))
    )
    (net (code "77") (name "unconnected-(U1-BDBUS6-Pad45)") (class "Default")
      (node (ref "U1") (pin "45") (pinfunction "BDBUS6_45") (pintype "input+no_connect"))
    )
    (net (code "78") (name "unconnected-(U1-BDBUS7-Pad46)") (class "Default")
      (node (ref "U1") (pin "46") (pinfunction "BDBUS7_46") (pintype "input+no_connect"))
    )
    (net (code "79") (name "unconnected-(U1-PWREN#-Pad60)") (class "Default")
      (node (ref "U1") (pin "60") (pinfunction "PWREN#_60") (pintype "input+no_connect"))
    )
    (net (code "80") (name "unconnected-(U1-SUSPEND#-Pad36)") (class "Default")
      (node (ref "U1") (pin "36") (pinfunction "SUSPEND#_36") (pintype "input+no_connect"))
    )
    (net (code "81") (name "unconnected-(U2-FAULT#-Pad3)") (class "Default")
      (node (ref "U2") (pin "3") (pinfunction "FAULT#_3") (pintype "input+no_connect"))
    )
    (net (code "82") (name "unconnected-(U3-NC-Pad4)") (class "Default")
      (node (ref "U3") (pin "4") (pinfunction "NC_4") (pintype "input+no_connect"))
    )
    (net (code "83") (name "unconnected-(USB1-SBU1-Pad9)") (class "Default")
      (node (ref "USB1") (pin "9") (pinfunction "SBU1_9") (pintype "unspecified+no_connect"))
    )
    (net (code "84") (name "unconnected-(USB1-SBU2-Pad3)") (class "Default")
      (node (ref "USB1") (pin "3") (pinfunction "SBU2_3") (pintype "unspecified+no_connect"))
    )
  )
)
